# led_boost.net
KiCad netlist of a schematic drawn in Altium Designer
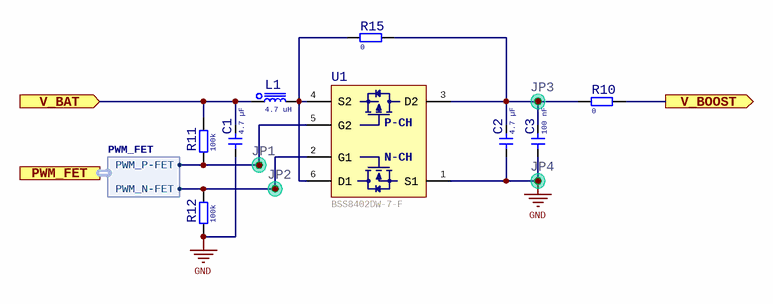
[diagram p0: led_boost.SchDoc]

(export (version "E")
  (design (tool "Eeschema 10.0.6"))
  (components
    (comp (ref "C1")
      (value "4.7 µF")
      (footprint "1608C")
      (description "SMD ceramic capacitor, X5R")
      (fields (field (name "MANUFACTURER") "Samsung") (field (name "VOLTAGE") "10"))
      (libsource (lib "Contronix") (part "CAP-NP"))
    )
    (comp (ref "C2")
      (value "4.7 µF")
      (footprint "1608C")
      (description "SMD ceramic capacitor, X5R")
      (fields (field (name "MANUFACTURER") "Samsung") (field (name "VOLTAGE") "10"))
      (libsource (lib "Contronix") (part "CAP-NP"))
    )
    (comp (ref "C3")
      (value "100 nF")
      (footprint "1608C")
      (description "SMD ceramic capacitor")
      (fields (field (name "MANUFACTURER") "Samsung") (field (name "VOLTAGE") "16"))
      (libsource (lib "Contronix") (part "CAP-NP"))
    )
    (comp (ref "JP1")
      (value "CON-01-TESTPOINT")
      (footprint "CON-01-PAD-1.3MM-1MM")
      (description "1.3 mm rund mit 1.0 mm Bohrung")
      (libsource (lib "Contronix") (part "CON-01-TESTPOINT"))
    )
    (comp (ref "JP2")
      (value "CON-01-TESTPOINT")
      (footprint "CON-01-PAD-1.3MM-1MM")
      (description "1.3 mm rund mit 1.0 mm Bohrung")
      (libsource (lib "Contronix") (part "CON-01-TESTPOINT"))
    )
    (comp (ref "JP3")
      (value "CON-01-TESTPOINT")
      (footprint "CON-01-PAD-1.3MM-1MM")
      (description "1.3 mm rund mit 1.0 mm Bohrung")
      (libsource (lib "Contronix") (part "CON-01-TESTPOINT"))
    )
    (comp (ref "JP4")
      (value "CON-01-TESTPOINT")
      (footprint "CON-01-PAD-1.3MM-1MM")
      (description "1.3 mm rund mit 1.0 mm Bohrung")
      (libsource (lib "Contronix") (part "CON-01-TESTPOINT"))
    )
    (comp (ref "L1")
      (value "4.7 uH")
      (footprint "2012L")
      (description "Chip Inductor")
      (fields (field (name "MANUFACTURER") "Murata Electronics") (field (name "TOLERANCE") "30%"))
      (libsource (lib "Contronix") (part "INDUCTOR"))
    )
    (comp (ref "R10")
      (value "0")
      (footprint "1608R")
      (description "SMD resistor")
      (fields (field (name "MANUFACTURER") "Bourns Inc.") (field (name "POWER") "0,1"))
      (libsource (lib "Contronix") (part "RES"))
    )
    (comp (ref "R11")
      (value "100k")
      (footprint "1608R")
      (description "SMD resistor")
      (fields (field (name "MANUFACTURER") "Panasonic - ECG") (field (name "TOLERANCE") "1%"))
      (libsource (lib "") (part "RES_1"))
    )
    (comp (ref "R12")
      (value "100k")
      (footprint "1608R")
      (description "SMD resistor")
      (fields (field (name "MANUFACTURER") "Panasonic - ECG") (field (name "TOLERANCE") "1%"))
      (libsource (lib "") (part "RES_1"))
    )
    (comp (ref "R15")
      (value "0")
      (footprint "1608R")
      (description "SMD resistor")
      (fields (field (name "MANUFACTURER") "Bourns Inc.") (field (name "POWER") "0,1"))
      (libsource (lib "Contronix") (part "RES"))
    )
    (comp (ref "U1")
      (value "TRANS-FET-DUAL-N-P-6PIN")
      (footprint "TRANS-DUAL-SOT-363-6")
      (description "N and P-Channel MOSFET")
      (fields
        (field (name "MANUFACTURER") "Diodes Inc.")
        (field (name "MANUFACTURER PART NUMBER") "BSS8402DW-7-F")
      )
      (libsource (lib "Transistors") (part "TRANS-FET-DUAL-N-P-6PIN"))
    )
  )
  (nets
    (net (code "2") (name "/V_BAT") (class "Default")
      (node (ref "C1") (pin "2") (pinfunction "2_2") (pintype "passive"))
      (node (ref "L1") (pin "1") (pinfunction "1_1") (pintype "passive"))
      (node (ref "R11") (pin "2") (pinfunction "2_2") (pintype "passive"))
    )
    (net (code "3") (name "/V_BOOST") (class "Default")
      (node (ref "R10") (pin "2") (pinfunction "2_2") (pintype "passive"))
    )
    (net (code "5") (name "GND") (class "Default")
      (node (ref "C1") (pin "1") (pinfunction "1_1") (pintype "passive"))
      (node (ref "C2") (pin "1") (pinfunction "1_1") (pintype "passive"))
      (node (ref "C3") (pin "1") (pinfunction "1_1") (pintype "passive"))
      (node (ref "JP4") (pin "1") (pinfunction "1_1") (pintype "passive"))
      (node (ref "R12") (pin "1") (pinfunction "1_1") (pintype "passive"))
      (node (ref "U1") (pin "1") (pinfunction "S1_1") (pintype "passive"))
    )
    (net (code "6") (name "Net-(U1-D1)") (class "Default")
      (node (ref "L1") (pin "2") (pinfunction "2_2") (pintype "passive"))
      (node (ref "R15") (pin "1") (pinfunction "1_1") (pintype "passive"))
      (node (ref "U1") (pin "4") (pinfunction "S2_4") (pintype "passive"))
      (node (ref "U1") (pin "6") (pinfunction "D1_6") (pintype "passive"))
    )
    (net (code "7") (name "Net-(U1-D2)") (class "Default")
      (node (ref "C2") (pin "2") (pinfunction "2_2") (pintype "passive"))
      (node (ref "C3") (pin "2") (pinfunction "2_2") (pintype "passive"))
      (node (ref "JP3") (pin "1") (pinfunction "1_1") (pintype "passive"))
      (node (ref "R10") (pin "1") (pinfunction "1_1") (pintype "passive"))
      (node (ref "R15") (pin "2") (pinfunction "2_2") (pintype "passive"))
      (node (ref "U1") (pin "3") (pinfunction "D2_3") (pintype "passive"))
    )
    (net (code "8") (name "Net-(U1-G1)") (class "Default")
      (node (ref "JP2") (pin "1") (pinfunction "1_1") (pintype "passive"))
      (node (ref "R12") (pin "2") (pinfunction "2_2") (pintype "passive"))
      (node (ref "U1") (pin "2") (pinfunction "G1_2") (pintype "passive"))
    )
    (net (code "9") (name "Net-(U1-G2)") (class "Default")
      (node (ref "JP1") (pin "1") (pinfunction "1_1") (pintype "passive"))
      (node (ref "R11") (pin "1") (pinfunction "1_1") (pintype "passive"))
      (node (ref "U1") (pin "5") (pinfunction "G2_5") (pintype "passive"))
    )
  )
)
